# Adafruit_TFT144_Breakout.net
KiCad netlist of a schematic drawn in EAGLE
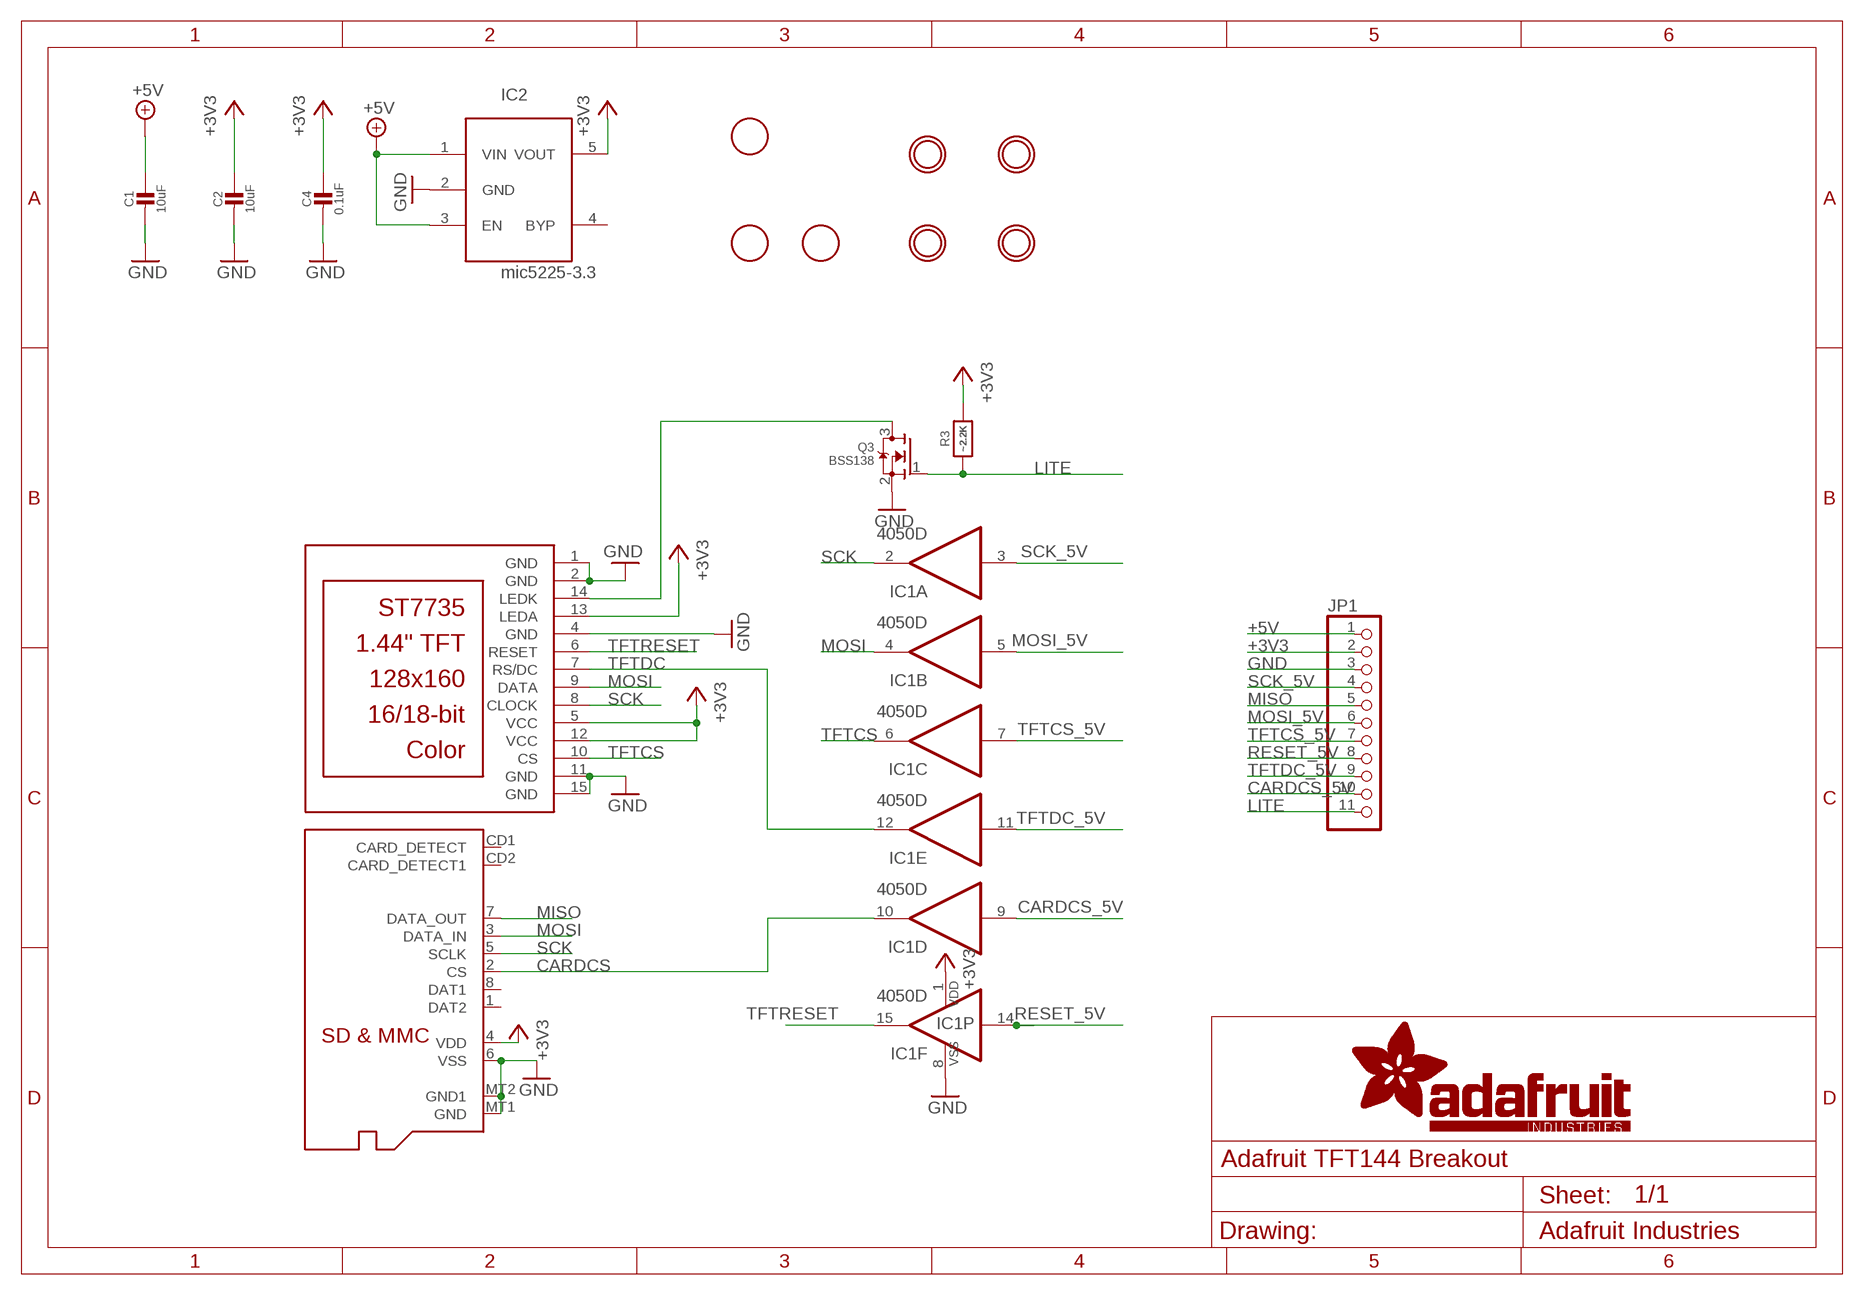
[diagram p0: schematic, sheet 1]

(export (version "E")
  (design (tool "Eeschema 10.0.6"))
  (components
    (comp (ref "C1")
      (value "10uF")
      (footprint "eagle-import:0805-NO")
      (libsource (lib "eagle-import") (part "CAP_CERAMIC0805-NOOUTLINE"))
    )
    (comp (ref "C2")
      (value "10uF")
      (footprint "eagle-import:0805-NO")
      (libsource (lib "eagle-import") (part "CAP_CERAMIC0805-NOOUTLINE"))
    )
    (comp (ref "C4")
      (value "0.1uF")
      (footprint "eagle-import:0805-NO")
      (libsource (lib "eagle-import") (part "CAP_CERAMIC0805-NOOUTLINE"))
    )
    (comp (ref "IC1")
      (value "4050D")
      (footprint "eagle-import:SO16")
      (libsource (lib "eagle-import") (part "4050D"))
    )
    (comp (ref "IC2")
      (value "mic5225-3.3")
      (footprint "eagle-import:SOT23-5L")
      (libsource (lib "eagle-import") (part "LP298XS"))
    )
    (comp (ref "JP1")
      (value "HEADER-1X1176MIL")
      (footprint "eagle-import:1X11_ROUND_76")
      (libsource (lib "eagle-import") (part "HEADER-1X1176MIL"))
    )
    (comp (ref "Q2")
      (value "MICROSD")
      (footprint "eagle-import:MICROSD")
      (libsource (lib "eagle-import") (part "MICROSD"))
    )
    (comp (ref "Q3")
      (value "BSS138")
      (footprint "eagle-import:SOT23-WIDE")
      (libsource (lib "eagle-import") (part "MOSFET-NWIDE"))
    )
    (comp (ref "R3")
      (value "~2.2K")
      (footprint "eagle-import:0805-NO")
      (libsource (lib "eagle-import") (part "RESISTOR0805_NOOUTLINE"))
    )
    (comp (ref "TFT2")
      (value "DISP_LCD_FPC1441609")
      (footprint "eagle-import:TFT_FPC1441609")
      (libsource (lib "eagle-import") (part "DISP_LCD_FPC1441609"))
    )
    (comp (ref "U$3")
      (value "FIDUCIAL")
      (footprint "eagle-import:FIDUCIAL_1MM")
      (libsource (lib "eagle-import") (part "FIDUCIAL"))
    )
    (comp (ref "U$4")
      (value "FIDUCIAL")
      (footprint "eagle-import:FIDUCIAL_1MM")
      (libsource (lib "eagle-import") (part "FIDUCIAL"))
    )
    (comp (ref "U$5")
      (value "FIDUCIAL")
      (footprint "eagle-import:FIDUCIAL_1MM")
      (libsource (lib "eagle-import") (part "FIDUCIAL"))
    )
    (comp (ref "U$7")
      (value "MOUNTINGHOLE2.5")
      (footprint "eagle-import:MOUNTINGHOLE_2.5_PLATED")
      (libsource (lib "eagle-import") (part "MOUNTINGHOLE2.5"))
    )
    (comp (ref "U$8")
      (value "MOUNTINGHOLE2.5")
      (footprint "eagle-import:MOUNTINGHOLE_2.5_PLATED")
      (libsource (lib "eagle-import") (part "MOUNTINGHOLE2.5"))
    )
    (comp (ref "U$9")
      (value "MOUNTINGHOLE2.5")
      (footprint "eagle-import:MOUNTINGHOLE_2.5_PLATED")
      (libsource (lib "eagle-import") (part "MOUNTINGHOLE2.5"))
    )
    (comp (ref "U$10")
      (value "MOUNTINGHOLE2.5")
      (footprint "eagle-import:MOUNTINGHOLE_2.5_PLATED")
      (libsource (lib "eagle-import") (part "MOUNTINGHOLE2.5"))
    )
  )
  (nets
    (net (code "1") (name "+3V3") (class "Default")
      (node (ref "C2") (pin "1") (pinfunction "1_1") (pintype "passive"))
      (node (ref "C4") (pin "1") (pinfunction "1_1") (pintype "passive"))
      (node (ref "IC1") (pin "1") (pinfunction "VDD_1") (pintype "power_in"))
      (node (ref "IC2") (pin "5") (pinfunction "VOUT_5") (pintype "bidirectional"))
      (node (ref "JP1") (pin "2") (pinfunction "2_2") (pintype "passive"))
      (node (ref "Q2") (pin "4") (pinfunction "VDD_4") (pintype "power_in"))
      (node (ref "R3") (pin "2") (pinfunction "2_2") (pintype "passive"))
      (node (ref "TFT2") (pin "12") (pinfunction "VCC_12") (pintype "power_in"))
      (node (ref "TFT2") (pin "13") (pinfunction "LEDA_13") (pintype "input"))
      (node (ref "TFT2") (pin "5") (pinfunction "VCC_5") (pintype "power_in"))
    )
    (net (code "2") (name "+5V") (class "Default")
      (node (ref "C1") (pin "1") (pinfunction "1_1") (pintype "passive"))
      (node (ref "IC2") (pin "1") (pinfunction "VIN_1") (pintype "bidirectional"))
      (node (ref "IC2") (pin "3") (pinfunction "EN_3") (pintype "bidirectional"))
      (node (ref "JP1") (pin "1") (pinfunction "1_1") (pintype "passive"))
    )
    (net (code "3") (name "/CARDCS") (class "Default")
      (node (ref "IC1") (pin "10") (pinfunction "O_10") (pintype "output"))
      (node (ref "Q2") (pin "2") (pinfunction "CS_2") (pintype "input"))
    )
    (net (code "4") (name "/CARDCS_5V") (class "Default")
      (node (ref "IC1") (pin "9") (pinfunction "I_9") (pintype "input"))
      (node (ref "JP1") (pin "10") (pinfunction "10_10") (pintype "passive"))
    )
    (net (code "5") (name "/LITE") (class "Default")
      (node (ref "JP1") (pin "11") (pinfunction "11_11") (pintype "passive"))
      (node (ref "Q3") (pin "1") (pinfunction "G_1") (pintype "bidirectional"))
      (node (ref "R3") (pin "1") (pinfunction "1_1") (pintype "passive"))
    )
    (net (code "6") (name "/MISO") (class "Default")
      (node (ref "JP1") (pin "5") (pinfunction "5_5") (pintype "passive"))
      (node (ref "Q2") (pin "7") (pinfunction "DATA_OUT_7") (pintype "output"))
    )
    (net (code "7") (name "/MOSI") (class "Default")
      (node (ref "IC1") (pin "4") (pinfunction "O_4") (pintype "output"))
      (node (ref "Q2") (pin "3") (pinfunction "DATA_IN_3") (pintype "input"))
      (node (ref "TFT2") (pin "9") (pinfunction "DATA_9") (pintype "bidirectional"))
    )
    (net (code "8") (name "/MOSI_5V") (class "Default")
      (node (ref "IC1") (pin "5") (pinfunction "I_5") (pintype "input"))
      (node (ref "JP1") (pin "6") (pinfunction "6_6") (pintype "passive"))
    )
    (net (code "9") (name "/RESET_5V") (class "Default")
      (node (ref "IC1") (pin "14") (pinfunction "I_14") (pintype "input"))
      (node (ref "JP1") (pin "8") (pinfunction "8_8") (pintype "passive"))
    )
    (net (code "10") (name "/SCK") (class "Default")
      (node (ref "IC1") (pin "2") (pinfunction "O_2") (pintype "output"))
      (node (ref "Q2") (pin "5") (pinfunction "SCLK_5") (pintype "input"))
      (node (ref "TFT2") (pin "8") (pinfunction "CLOCK_8") (pintype "input"))
    )
    (net (code "11") (name "/SCK_5V") (class "Default")
      (node (ref "IC1") (pin "3") (pinfunction "I_3") (pintype "input"))
      (node (ref "JP1") (pin "4") (pinfunction "4_4") (pintype "passive"))
    )
    (net (code "12") (name "/TFTCS") (class "Default")
      (node (ref "IC1") (pin "6") (pinfunction "O_6") (pintype "output"))
      (node (ref "TFT2") (pin "10") (pinfunction "CS_10") (pintype "input"))
    )
    (net (code "13") (name "/TFTCS_5V") (class "Default")
      (node (ref "IC1") (pin "7") (pinfunction "I_7") (pintype "input"))
      (node (ref "JP1") (pin "7") (pinfunction "7_7") (pintype "passive"))
    )
    (net (code "14") (name "/TFTDC") (class "Default")
      (node (ref "IC1") (pin "12") (pinfunction "O_12") (pintype "output"))
      (node (ref "TFT2") (pin "7") (pinfunction "RS/DC_7") (pintype "input"))
    )
    (net (code "15") (name "/TFTDC_5V") (class "Default")
      (node (ref "IC1") (pin "11") (pinfunction "I_11") (pintype "input"))
      (node (ref "JP1") (pin "9") (pinfunction "9_9") (pintype "passive"))
    )
    (net (code "16") (name "/TFTRESET") (class "Default")
      (node (ref "IC1") (pin "15") (pinfunction "O_15") (pintype "output"))
      (node (ref "TFT2") (pin "6") (pinfunction "RESET_6") (pintype "input"))
    )
    (net (code "17") (name "GND") (class "Default")
      (node (ref "C1") (pin "2") (pinfunction "2_2") (pintype "passive"))
      (node (ref "C2") (pin "2") (pinfunction "2_2") (pintype "passive"))
      (node (ref "C4") (pin "2") (pinfunction "2_2") (pintype "passive"))
      (node (ref "IC1") (pin "8") (pinfunction "VSS_8") (pintype "power_in"))
      (node (ref "IC2") (pin "2") (pinfunction "GND_2") (pintype "bidirectional"))
      (node (ref "JP1") (pin "3") (pinfunction "3_3") (pintype "passive"))
      (node (ref "Q2") (pin "6") (pinfunction "VSS_6") (pintype "power_in"))
      (node (ref "Q2") (pin "MT1") (pinfunction "GND_MT1") (pintype "power_in"))
      (node (ref "Q2") (pin "MT2") (pinfunction "GND1_MT2") (pintype "power_in"))
      (node (ref "Q3") (pin "2") (pinfunction "S_2") (pintype "bidirectional"))
      (node (ref "TFT2") (pin "1") (pinfunction "GND_1") (pintype "power_in"))
      (node (ref "TFT2") (pin "11") (pinfunction "GND_11") (pintype "power_in"))
      (node (ref "TFT2") (pin "15") (pinfunction "GND_15") (pintype "power_in"))
      (node (ref "TFT2") (pin "2") (pinfunction "GND_2") (pintype "power_in"))
      (node (ref "TFT2") (pin "4") (pinfunction "GND_4") (pintype "power_in"))
    )
    (net (code "18") (name "Net-(Q3-D)") (class "Default")
      (node (ref "Q3") (pin "3") (pinfunction "D_3") (pintype "bidirectional"))
      (node (ref "TFT2") (pin "14") (pinfunction "LEDK_14") (pintype "input"))
    )
    (net (code "19") (name "unconnected-(IC2-BYP-Pad4)") (class "Default")
      (node (ref "IC2") (pin "4") (pinfunction "BYP_4") (pintype "bidirectional"))
    )
    (net (code "20") (name "unconnected-(Q2-CARD_DETECT-PadCD1)") (class "Default")
      (node (ref "Q2") (pin "CD1") (pinfunction "CARD_DETECT_CD1") (pintype "passive"))
    )
    (net (code "21") (name "unconnected-(Q2-CARD_DETECT1-PadCD2)") (class "Default")
      (node (ref "Q2") (pin "CD2") (pinfunction "CARD_DETECT1_CD2") (pintype "passive"))
    )
    (net (code "22") (name "unconnected-(Q2-DAT1-Pad8)") (class "Default")
      (node (ref "Q2") (pin "8") (pinfunction "DAT1_8") (pintype "bidirectional"))
    )
    (net (code "23") (name "unconnected-(Q2-DAT2-Pad1)") (class "Default")
      (node (ref "Q2") (pin "1") (pinfunction "DAT2_1") (pintype "bidirectional"))
    )
  )
)
